# 3_phase.net
KiCad netlist of a schematic drawn in EAGLE
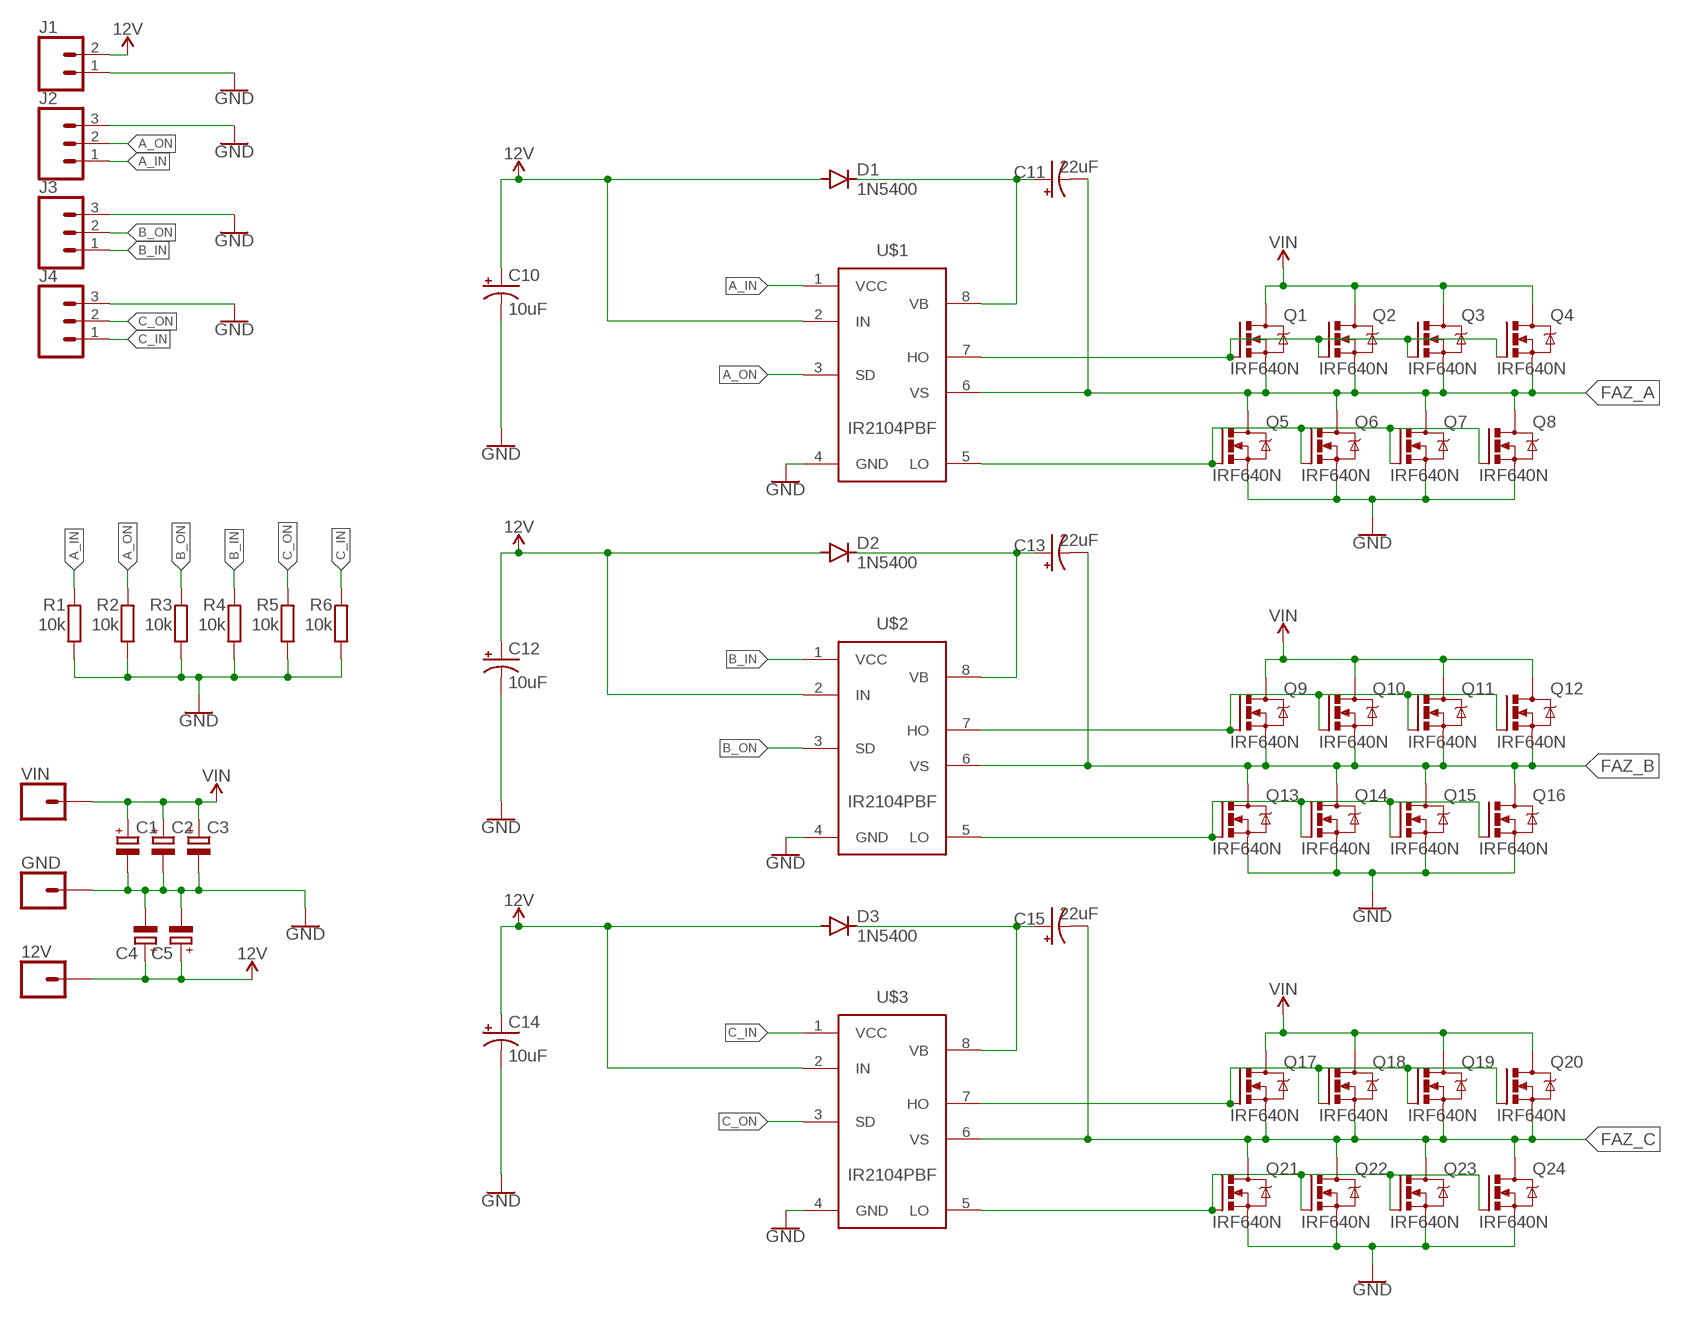
[diagram p0: schematic, sheet 1]

(export (version "E")
  (design (tool "Eeschema 10.0.6"))
  (components
    (comp (ref "12V")
      (value "CONN_01SNAP-MALE")
      (footprint "eagle-import:SNAP-MALE")
      (libsource (lib "eagle-import") (part "CONN_01SNAP-MALE"))
    )
    (comp (ref "C1")
      (value "16MM-DIA-CAPASITOR")
      (footprint "eagle-import:16MM-DIA-CAPASITOR")
      (libsource (lib "eagle-import") (part "16MM-DIA-CAPASITOR"))
    )
    (comp (ref "C2")
      (value "16MM-DIA-CAPASITOR")
      (footprint "eagle-import:16MM-DIA-CAPASITOR")
      (libsource (lib "eagle-import") (part "16MM-DIA-CAPASITOR"))
    )
    (comp (ref "C3")
      (value "16MM-DIA-CAPASITOR")
      (footprint "eagle-import:16MM-DIA-CAPASITOR")
      (libsource (lib "eagle-import") (part "16MM-DIA-CAPASITOR"))
    )
    (comp (ref "C4")
      (value "16MM-DIA-CAPASITOR")
      (footprint "eagle-import:16MM-DIA-CAPASITOR")
      (libsource (lib "eagle-import") (part "16MM-DIA-CAPASITOR"))
    )
    (comp (ref "C5")
      (value "16MM-DIA-CAPASITOR")
      (footprint "eagle-import:16MM-DIA-CAPASITOR")
      (libsource (lib "eagle-import") (part "16MM-DIA-CAPASITOR"))
    )
    (comp (ref "C10")
      (value "10uF")
      (footprint "eagle-import:CPOL-RADIAL-2.5MM-5MM")
      (libsource (lib "eagle-import") (part "10UF-POLAR-RADIAL-2.5MM-25V-20%"))
    )
    (comp (ref "C11")
      (value "22uF")
      (footprint "eagle-import:CPOL-RADIAL-2.5MM-5MM")
      (libsource (lib "eagle-import") (part "10UF-POLAR-RADIAL-2.5MM-25V-20%"))
    )
    (comp (ref "C12")
      (value "10uF")
      (footprint "eagle-import:CPOL-RADIAL-2.5MM-5MM")
      (libsource (lib "eagle-import") (part "10UF-POLAR-RADIAL-2.5MM-25V-20%"))
    )
    (comp (ref "C13")
      (value "22uF")
      (footprint "eagle-import:CPOL-RADIAL-2.5MM-5MM")
      (libsource (lib "eagle-import") (part "10UF-POLAR-RADIAL-2.5MM-25V-20%"))
    )
    (comp (ref "C14")
      (value "10uF")
      (footprint "eagle-import:CPOL-RADIAL-2.5MM-5MM")
      (libsource (lib "eagle-import") (part "10UF-POLAR-RADIAL-2.5MM-25V-20%"))
    )
    (comp (ref "C15")
      (value "22uF")
      (footprint "eagle-import:CPOL-RADIAL-2.5MM-5MM")
      (libsource (lib "eagle-import") (part "10UF-POLAR-RADIAL-2.5MM-25V-20%"))
    )
    (comp (ref "D1")
      (value "1N5400")
      (footprint "eagle-import:DO201-15")
      (libsource (lib "eagle-import") (part "1N5400"))
    )
    (comp (ref "D2")
      (value "1N5400")
      (footprint "eagle-import:DO201-15")
      (libsource (lib "eagle-import") (part "1N5400"))
    )
    (comp (ref "D3")
      (value "1N5400")
      (footprint "eagle-import:DO201-15")
      (libsource (lib "eagle-import") (part "1N5400"))
    )
    (comp (ref "GND")
      (value "CONN_01SNAP-MALE")
      (footprint "eagle-import:SNAP-MALE")
      (libsource (lib "eagle-import") (part "CONN_01SNAP-MALE"))
    )
    (comp (ref "J1")
      (value "CONN_025MM")
      (footprint "eagle-import:SCREWTERMINAL-5MM-2")
      (libsource (lib "eagle-import") (part "CONN_025MM"))
    )
    (comp (ref "J2")
      (value "CONN_03-SCREW-5MM")
      (footprint "eagle-import:SCREWTERMINAL-5MM-3")
      (libsource (lib "eagle-import") (part "CONN_03-SCREW-5MM"))
    )
    (comp (ref "J3")
      (value "CONN_03-SCREW-5MM")
      (footprint "eagle-import:SCREWTERMINAL-5MM-3")
      (libsource (lib "eagle-import") (part "CONN_03-SCREW-5MM"))
    )
    (comp (ref "J4")
      (value "CONN_03-SCREW-5MM")
      (footprint "eagle-import:SCREWTERMINAL-5MM-3")
      (libsource (lib "eagle-import") (part "CONN_03-SCREW-5MM"))
    )
    (comp (ref "Q1")
      (value "IRF640N")
      (footprint "eagle-import:TO-220-PAD")
      (libsource (lib "eagle-import") (part "IRF640N"))
    )
    (comp (ref "Q2")
      (value "IRF640N")
      (footprint "eagle-import:TO-220-PAD")
      (libsource (lib "eagle-import") (part "IRF640N"))
    )
    (comp (ref "Q3")
      (value "IRF640N")
      (footprint "eagle-import:TO-220-PAD")
      (libsource (lib "eagle-import") (part "IRF640N"))
    )
    (comp (ref "Q4")
      (value "IRF640N")
      (footprint "eagle-import:TO-220-PAD")
      (libsource (lib "eagle-import") (part "IRF640N"))
    )
    (comp (ref "Q5")
      (value "IRF640N")
      (footprint "eagle-import:TO-220-PAD")
      (libsource (lib "eagle-import") (part "IRF640N"))
    )
    (comp (ref "Q6")
      (value "IRF640N")
      (footprint "eagle-import:TO-220-PAD")
      (libsource (lib "eagle-import") (part "IRF640N"))
    )
    (comp (ref "Q7")
      (value "IRF640N")
      (footprint "eagle-import:TO-220-PAD")
      (libsource (lib "eagle-import") (part "IRF640N"))
    )
    (comp (ref "Q8")
      (value "IRF640N")
      (footprint "eagle-import:TO-220-PAD")
      (libsource (lib "eagle-import") (part "IRF640N"))
    )
    (comp (ref "Q9")
      (value "IRF640N")
      (footprint "eagle-import:TO-220-PAD")
      (libsource (lib "eagle-import") (part "IRF640N"))
    )
    (comp (ref "Q10")
      (value "IRF640N")
      (footprint "eagle-import:TO-220-PAD")
      (libsource (lib "eagle-import") (part "IRF640N"))
    )
    (comp (ref "Q11")
      (value "IRF640N")
      (footprint "eagle-import:TO-220-PAD")
      (libsource (lib "eagle-import") (part "IRF640N"))
    )
    (comp (ref "Q12")
      (value "IRF640N")
      (footprint "eagle-import:TO-220-PAD")
      (libsource (lib "eagle-import") (part "IRF640N"))
    )
    (comp (ref "Q13")
      (value "IRF640N")
      (footprint "eagle-import:TO-220-PAD")
      (libsource (lib "eagle-import") (part "IRF640N"))
    )
    (comp (ref "Q14")
      (value "IRF640N")
      (footprint "eagle-import:TO-220-PAD")
      (libsource (lib "eagle-import") (part "IRF640N"))
    )
    (comp (ref "Q15")
      (value "IRF640N")
      (footprint "eagle-import:TO-220-PAD")
      (libsource (lib "eagle-import") (part "IRF640N"))
    )
    (comp (ref "Q16")
      (value "IRF640N")
      (footprint "eagle-import:TO-220-PAD")
      (libsource (lib "eagle-import") (part "IRF640N"))
    )
    (comp (ref "Q17")
      (value "IRF640N")
      (footprint "eagle-import:TO-220-PAD")
      (libsource (lib "eagle-import") (part "IRF640N"))
    )
    (comp (ref "Q18")
      (value "IRF640N")
      (footprint "eagle-import:TO-220-PAD")
      (libsource (lib "eagle-import") (part "IRF640N"))
    )
    (comp (ref "Q19")
      (value "IRF640N")
      (footprint "eagle-import:TO-220-PAD")
      (libsource (lib "eagle-import") (part "IRF640N"))
    )
    (comp (ref "Q20")
      (value "IRF640N")
      (footprint "eagle-import:TO-220-PAD")
      (libsource (lib "eagle-import") (part "IRF640N"))
    )
    (comp (ref "Q21")
      (value "IRF640N")
      (footprint "eagle-import:TO-220-PAD")
      (libsource (lib "eagle-import") (part "IRF640N"))
    )
    (comp (ref "Q22")
      (value "IRF640N")
      (footprint "eagle-import:TO-220-PAD")
      (libsource (lib "eagle-import") (part "IRF640N"))
    )
    (comp (ref "Q23")
      (value "IRF640N")
      (footprint "eagle-import:TO-220-PAD")
      (libsource (lib "eagle-import") (part "IRF640N"))
    )
    (comp (ref "Q24")
      (value "IRF640N")
      (footprint "eagle-import:TO-220-PAD")
      (libsource (lib "eagle-import") (part "IRF640N"))
    )
    (comp (ref "R1")
      (value "10k")
      (footprint "eagle-import:0207_10")
      (libsource (lib "eagle-import") (part "R-EU_0207/10"))
    )
    (comp (ref "R2")
      (value "10k")
      (footprint "eagle-import:0207_10")
      (libsource (lib "eagle-import") (part "R-EU_0207/10"))
    )
    (comp (ref "R3")
      (value "10k")
      (footprint "eagle-import:0207_10")
      (libsource (lib "eagle-import") (part "R-EU_0207/10"))
    )
    (comp (ref "R4")
      (value "10k")
      (footprint "eagle-import:0207_10")
      (libsource (lib "eagle-import") (part "R-EU_0207/10"))
    )
    (comp (ref "R5")
      (value "10k")
      (footprint "eagle-import:0207_10")
      (libsource (lib "eagle-import") (part "R-EU_0207/10"))
    )
    (comp (ref "R6")
      (value "10k")
      (footprint "eagle-import:0207_10")
      (libsource (lib "eagle-import") (part "R-EU_0207/10"))
    )
    (comp (ref "U$1")
      (value "IR2104PBF")
      (footprint "eagle-import:DIP-8")
      (libsource (lib "eagle-import") (part "IR2104PBF"))
    )
    (comp (ref "U$2")
      (value "IR2104PBF")
      (footprint "eagle-import:DIP-8")
      (libsource (lib "eagle-import") (part "IR2104PBF"))
    )
    (comp (ref "U$3")
      (value "IR2104PBF")
      (footprint "eagle-import:DIP-8")
      (libsource (lib "eagle-import") (part "IR2104PBF"))
    )
    (comp (ref "VIN")
      (value "CONN_01SNAP-MALE")
      (footprint "eagle-import:SNAP-MALE")
      (libsource (lib "eagle-import") (part "CONN_01SNAP-MALE"))
    )
  )
  (nets
    (net (code "1") (name "12V") (class "Default")
      (node (ref "12V") (pin "2") (pinfunction "1_2") (pintype "passive"))
      (node (ref "C10") (pin "1") (pinfunction "+_1") (pintype "passive"))
      (node (ref "C12") (pin "1") (pinfunction "+_1") (pintype "passive"))
      (node (ref "C14") (pin "1") (pinfunction "+_1") (pintype "passive"))
      (node (ref "C4") (pin "+") (pinfunction "+_+") (pintype "passive"))
      (node (ref "C5") (pin "+") (pinfunction "+_+") (pintype "passive"))
      (node (ref "D1") (pin "A") (pinfunction "A_A") (pintype "passive"))
      (node (ref "D2") (pin "A") (pinfunction "A_A") (pintype "passive"))
      (node (ref "D3") (pin "A") (pinfunction "A_A") (pintype "passive"))
      (node (ref "J1") (pin "2") (pinfunction "2_2") (pintype "passive"))
      (node (ref "U$1") (pin "2") (pinfunction "IN_2") (pintype "bidirectional"))
      (node (ref "U$2") (pin "2") (pinfunction "IN_2") (pintype "bidirectional"))
      (node (ref "U$3") (pin "2") (pinfunction "IN_2") (pintype "bidirectional"))
    )
    (net (code "2") (name "A_IN") (class "Default")
      (node (ref "J2") (pin "1") (pinfunction "1_1") (pintype "passive"))
      (node (ref "R1") (pin "2") (pinfunction "2_2") (pintype "passive"))
      (node (ref "U$1") (pin "1") (pinfunction "VCC_1") (pintype "bidirectional"))
    )
    (net (code "3") (name "A_ON") (class "Default")
      (node (ref "J2") (pin "2") (pinfunction "2_2") (pintype "passive"))
      (node (ref "R2") (pin "2") (pinfunction "2_2") (pintype "passive"))
      (node (ref "U$1") (pin "3") (pinfunction "SD_3") (pintype "bidirectional"))
    )
    (net (code "4") (name "B_IN") (class "Default")
      (node (ref "J3") (pin "1") (pinfunction "1_1") (pintype "passive"))
      (node (ref "R4") (pin "2") (pinfunction "2_2") (pintype "passive"))
      (node (ref "U$2") (pin "1") (pinfunction "VCC_1") (pintype "bidirectional"))
    )
    (net (code "5") (name "B_ON") (class "Default")
      (node (ref "J3") (pin "2") (pinfunction "2_2") (pintype "passive"))
      (node (ref "R3") (pin "2") (pinfunction "2_2") (pintype "passive"))
      (node (ref "U$2") (pin "3") (pinfunction "SD_3") (pintype "bidirectional"))
    )
    (net (code "6") (name "C_IN") (class "Default")
      (node (ref "J4") (pin "1") (pinfunction "1_1") (pintype "passive"))
      (node (ref "R6") (pin "2") (pinfunction "2_2") (pintype "passive"))
      (node (ref "U$3") (pin "1") (pinfunction "VCC_1") (pintype "bidirectional"))
    )
    (net (code "7") (name "C_ON") (class "Default")
      (node (ref "J4") (pin "2") (pinfunction "2_2") (pintype "passive"))
      (node (ref "R5") (pin "2") (pinfunction "2_2") (pintype "passive"))
      (node (ref "U$3") (pin "3") (pinfunction "SD_3") (pintype "bidirectional"))
    )
    (net (code "8") (name "FAZ_A") (class "Default")
      (node (ref "C11") (pin "2") (pinfunction "-_2") (pintype "passive"))
      (node (ref "Q1") (pin "3") (pinfunction "S_3") (pintype "passive"))
      (node (ref "Q2") (pin "3") (pinfunction "S_3") (pintype "passive"))
      (node (ref "Q3") (pin "3") (pinfunction "S_3") (pintype "passive"))
      (node (ref "Q4") (pin "3") (pinfunction "S_3") (pintype "passive"))
      (node (ref "Q5") (pin "TAB") (pinfunction "D_TAB") (pintype "passive"))
      (node (ref "Q6") (pin "TAB") (pinfunction "D_TAB") (pintype "passive"))
      (node (ref "Q7") (pin "TAB") (pinfunction "D_TAB") (pintype "passive"))
      (node (ref "Q8") (pin "TAB") (pinfunction "D_TAB") (pintype "passive"))
      (node (ref "U$1") (pin "6") (pinfunction "VS_6") (pintype "bidirectional"))
    )
    (net (code "9") (name "FAZ_B") (class "Default")
      (node (ref "C13") (pin "2") (pinfunction "-_2") (pintype "passive"))
      (node (ref "Q10") (pin "3") (pinfunction "S_3") (pintype "passive"))
      (node (ref "Q11") (pin "3") (pinfunction "S_3") (pintype "passive"))
      (node (ref "Q12") (pin "3") (pinfunction "S_3") (pintype "passive"))
      (node (ref "Q13") (pin "TAB") (pinfunction "D_TAB") (pintype "passive"))
      (node (ref "Q14") (pin "TAB") (pinfunction "D_TAB") (pintype "passive"))
      (node (ref "Q15") (pin "TAB") (pinfunction "D_TAB") (pintype "passive"))
      (node (ref "Q16") (pin "TAB") (pinfunction "D_TAB") (pintype "passive"))
      (node (ref "Q9") (pin "3") (pinfunction "S_3") (pintype "passive"))
      (node (ref "U$2") (pin "6") (pinfunction "VS_6") (pintype "bidirectional"))
    )
    (net (code "10") (name "FAZ_C") (class "Default")
      (node (ref "C15") (pin "2") (pinfunction "-_2") (pintype "passive"))
      (node (ref "Q17") (pin "3") (pinfunction "S_3") (pintype "passive"))
      (node (ref "Q18") (pin "3") (pinfunction "S_3") (pintype "passive"))
      (node (ref "Q19") (pin "3") (pinfunction "S_3") (pintype "passive"))
      (node (ref "Q20") (pin "3") (pinfunction "S_3") (pintype "passive"))
      (node (ref "Q21") (pin "TAB") (pinfunction "D_TAB") (pintype "passive"))
      (node (ref "Q22") (pin "TAB") (pinfunction "D_TAB") (pintype "passive"))
      (node (ref "Q23") (pin "TAB") (pinfunction "D_TAB") (pintype "passive"))
      (node (ref "Q24") (pin "TAB") (pinfunction "D_TAB") (pintype "passive"))
      (node (ref "U$3") (pin "6") (pinfunction "VS_6") (pintype "bidirectional"))
    )
    (net (code "11") (name "GND") (class "Default")
      (node (ref "C1") (pin "-") (pinfunction "-_-") (pintype "passive"))
      (node (ref "C10") (pin "2") (pinfunction "-_2") (pintype "passive"))
      (node (ref "C12") (pin "2") (pinfunction "-_2") (pintype "passive"))
      (node (ref "C14") (pin "2") (pinfunction "-_2") (pintype "passive"))
      (node (ref "C2") (pin "-") (pinfunction "-_-") (pintype "passive"))
      (node (ref "C3") (pin "-") (pinfunction "-_-") (pintype "passive"))
      (node (ref "C4") (pin "-") (pinfunction "-_-") (pintype "passive"))
      (node (ref "C5") (pin "-") (pinfunction "-_-") (pintype "passive"))
      (node (ref "GND") (pin "2") (pinfunction "1_2") (pintype "passive"))
      (node (ref "J1") (pin "1") (pinfunction "1_1") (pintype "passive"))
      (node (ref "J2") (pin "3") (pinfunction "3_3") (pintype "passive"))
      (node (ref "J3") (pin "3") (pinfunction "3_3") (pintype "passive"))
      (node (ref "J4") (pin "3") (pinfunction "3_3") (pintype "passive"))
      (node (ref "Q13") (pin "3") (pinfunction "S_3") (pintype "passive"))
      (node (ref "Q14") (pin "3") (pinfunction "S_3") (pintype "passive"))
      (node (ref "Q15") (pin "3") (pinfunction "S_3") (pintype "passive"))
      (node (ref "Q16") (pin "3") (pinfunction "S_3") (pintype "passive"))
      (node (ref "Q21") (pin "3") (pinfunction "S_3") (pintype "passive"))
      (node (ref "Q22") (pin "3") (pinfunction "S_3") (pintype "passive"))
      (node (ref "Q23") (pin "3") (pinfunction "S_3") (pintype "passive"))
      (node (ref "Q24") (pin "3") (pinfunction "S_3") (pintype "passive"))
      (node (ref "Q5") (pin "3") (pinfunction "S_3") (pintype "passive"))
      (node (ref "Q6") (pin "3") (pinfunction "S_3") (pintype "passive"))
      (node (ref "Q7") (pin "3") (pinfunction "S_3") (pintype "passive"))
      (node (ref "Q8") (pin "3") (pinfunction "S_3") (pintype "passive"))
      (node (ref "R1") (pin "1") (pinfunction "1_1") (pintype "passive"))
      (node (ref "R2") (pin "1") (pinfunction "1_1") (pintype "passive"))
      (node (ref "R3") (pin "1") (pinfunction "1_1") (pintype "passive"))
      (node (ref "R4") (pin "1") (pinfunction "1_1") (pintype "passive"))
      (node (ref "R5") (pin "1") (pinfunction "1_1") (pintype "passive"))
      (node (ref "R6") (pin "1") (pinfunction "1_1") (pintype "passive"))
      (node (ref "U$1") (pin "4") (pinfunction "GND_4") (pintype "bidirectional"))
      (node (ref "U$2") (pin "4") (pinfunction "GND_4") (pintype "bidirectional"))
      (node (ref "U$3") (pin "4") (pinfunction "GND_4") (pintype "bidirectional"))
    )
    (net (code "12") (name "Net-(C11-+)") (class "Default")
      (node (ref "C11") (pin "1") (pinfunction "+_1") (pintype "passive"))
      (node (ref "D1") (pin "C") (pinfunction "C_C") (pintype "passive"))
      (node (ref "U$1") (pin "8") (pinfunction "VB_8") (pintype "bidirectional"))
    )
    (net (code "13") (name "Net-(C13-+)") (class "Default")
      (node (ref "C13") (pin "1") (pinfunction "+_1") (pintype "passive"))
      (node (ref "D2") (pin "C") (pinfunction "C_C") (pintype "passive"))
      (node (ref "U$2") (pin "8") (pinfunction "VB_8") (pintype "bidirectional"))
    )
    (net (code "14") (name "Net-(C15-+)") (class "Default")
      (node (ref "C15") (pin "1") (pinfunction "+_1") (pintype "passive"))
      (node (ref "D3") (pin "C") (pinfunction "C_C") (pintype "passive"))
      (node (ref "U$3") (pin "8") (pinfunction "VB_8") (pintype "bidirectional"))
    )
    (net (code "15") (name "Net-(Q1-G)") (class "Default")
      (node (ref "Q1") (pin "1") (pinfunction "G_1") (pintype "passive"))
      (node (ref "Q2") (pin "1") (pinfunction "G_1") (pintype "passive"))
      (node (ref "Q3") (pin "1") (pinfunction "G_1") (pintype "passive"))
      (node (ref "Q4") (pin "1") (pinfunction "G_1") (pintype "passive"))
      (node (ref "U$1") (pin "7") (pinfunction "HO_7") (pintype "bidirectional"))
    )
    (net (code "16") (name "Net-(Q5-G)") (class "Default")
      (node (ref "Q5") (pin "1") (pinfunction "G_1") (pintype "passive"))
      (node (ref "Q6") (pin "1") (pinfunction "G_1") (pintype "passive"))
      (node (ref "Q7") (pin "1") (pinfunction "G_1") (pintype "passive"))
      (node (ref "Q8") (pin "1") (pinfunction "G_1") (pintype "passive"))
      (node (ref "U$1") (pin "5") (pinfunction "LO_5") (pintype "bidirectional"))
    )
    (net (code "17") (name "Net-(Q10-G)") (class "Default")
      (node (ref "Q10") (pin "1") (pinfunction "G_1") (pintype "passive"))
      (node (ref "Q11") (pin "1") (pinfunction "G_1") (pintype "passive"))
      (node (ref "Q12") (pin "1") (pinfunction "G_1") (pintype "passive"))
      (node (ref "Q9") (pin "1") (pinfunction "G_1") (pintype "passive"))
      (node (ref "U$2") (pin "7") (pinfunction "HO_7") (pintype "bidirectional"))
    )
    (net (code "18") (name "Net-(Q13-G)") (class "Default")
      (node (ref "Q13") (pin "1") (pinfunction "G_1") (pintype "passive"))
      (node (ref "Q14") (pin "1") (pinfunction "G_1") (pintype "passive"))
      (node (ref "Q15") (pin "1") (pinfunction "G_1") (pintype "passive"))
      (node (ref "Q16") (pin "1") (pinfunction "G_1") (pintype "passive"))
      (node (ref "U$2") (pin "5") (pinfunction "LO_5") (pintype "bidirectional"))
    )
    (net (code "19") (name "Net-(Q17-G)") (class "Default")
      (node (ref "Q17") (pin "1") (pinfunction "G_1") (pintype "passive"))
      (node (ref "Q18") (pin "1") (pinfunction "G_1") (pintype "passive"))
      (node (ref "Q19") (pin "1") (pinfunction "G_1") (pintype "passive"))
      (node (ref "Q20") (pin "1") (pinfunction "G_1") (pintype "passive"))
      (node (ref "U$3") (pin "7") (pinfunction "HO_7") (pintype "bidirectional"))
    )
    (net (code "20") (name "Net-(Q21-G)") (class "Default")
      (node (ref "Q21") (pin "1") (pinfunction "G_1") (pintype "passive"))
      (node (ref "Q22") (pin "1") (pinfunction "G_1") (pintype "passive"))
      (node (ref "Q23") (pin "1") (pinfunction "G_1") (pintype "passive"))
      (node (ref "Q24") (pin "1") (pinfunction "G_1") (pintype "passive"))
      (node (ref "U$3") (pin "5") (pinfunction "LO_5") (pintype "bidirectional"))
    )
    (net (code "21") (name "VIN") (class "Default")
      (node (ref "C1") (pin "+") (pinfunction "+_+") (pintype "passive"))
      (node (ref "C2") (pin "+") (pinfunction "+_+") (pintype "passive"))
      (node (ref "C3") (pin "+") (pinfunction "+_+") (pintype "passive"))
      (node (ref "Q1") (pin "TAB") (pinfunction "D_TAB") (pintype "passive"))
      (node (ref "Q10") (pin "TAB") (pinfunction "D_TAB") (pintype "passive"))
      (node (ref "Q11") (pin "TAB") (pinfunction "D_TAB") (pintype "passive"))
      (node (ref "Q12") (pin "TAB") (pinfunction "D_TAB") (pintype "passive"))
      (node (ref "Q17") (pin "TAB") (pinfunction "D_TAB") (pintype "passive"))
      (node (ref "Q18") (pin "TAB") (pinfunction "D_TAB") (pintype "passive"))
      (node (ref "Q19") (pin "TAB") (pinfunction "D_TAB") (pintype "passive"))
      (node (ref "Q2") (pin "TAB") (pinfunction "D_TAB") (pintype "passive"))
      (node (ref "Q20") (pin "TAB") (pinfunction "D_TAB") (pintype "passive"))
      (node (ref "Q3") (pin "TAB") (pinfunction "D_TAB") (pintype "passive"))
      (node (ref "Q4") (pin "TAB") (pinfunction "D_TAB") (pintype "passive"))
      (node (ref "Q9") (pin "TAB") (pinfunction "D_TAB") (pintype "passive"))
      (node (ref "VIN") (pin "2") (pinfunction "1_2") (pintype "passive"))
    )
  )
)
